# IMU.net
KiCad netlist of a schematic drawn in Altium Designer
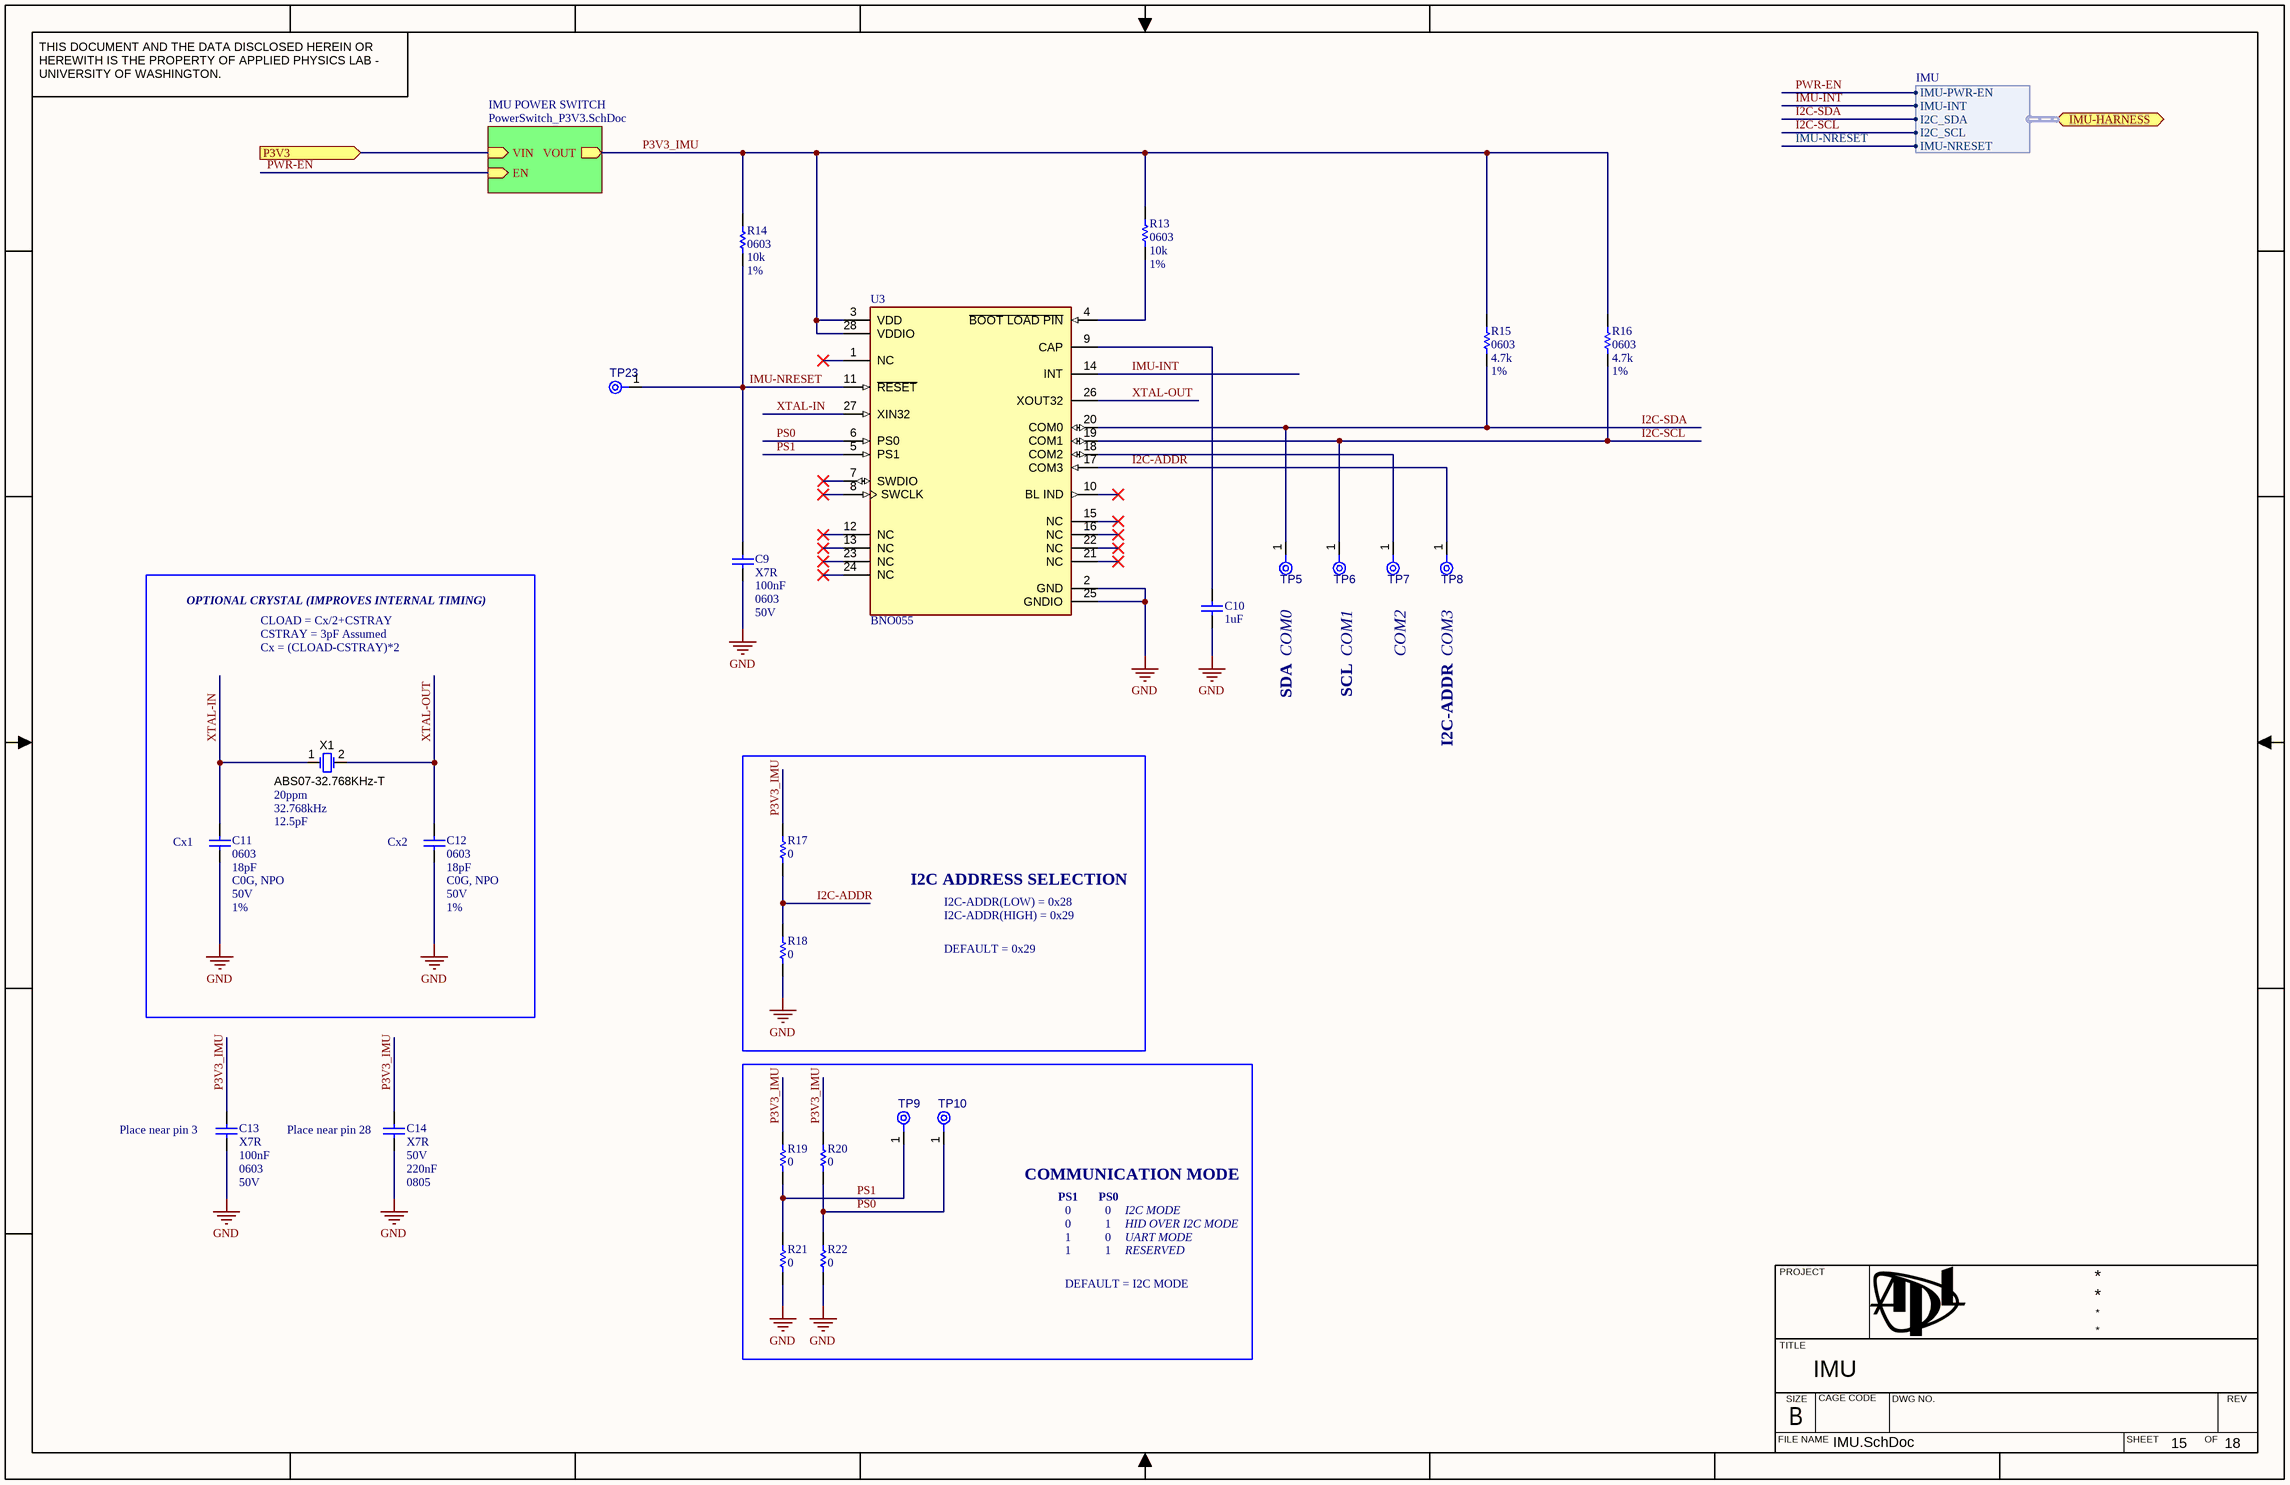
[diagram p0: IMU.SchDoc]

(export (version "E")
  (design (tool "Eeschema 10.0.6"))
  (components
    (comp (ref "C9")
      (value "100nF")
      (footprint "CAPC1608X90X40ML10T20")
      (description "Chip Capacitor, 100nF, +/- 10%, 50 V, X7R 0603 (1608 Metric)")
      (fields
        (field (name "DIELECTRIC") "X7R")
        (field (name "CASE/PACKAGE") "0603")
        (field (name "TOLERANCE") "10%")
        (field (name "VOLTAGE RATING") "50V")
        (field (name "Comment") "Capacitor 100nF +/- 10%, 50V, X7R, 0603")
      )
      (libsource (lib "Applied Physics Lab") (part "CAP-NP-2"))
    )
    (comp (ref "C10")
      (value "1uF")
      (footprint "CAPC2013X95X50ML10T25")
      (description "Chip Capacitor, 1uF, 10%, 50 V, X7R 0805 (2012 Metric)")
      (fields (field (name "TOLERANCE") "10%") (field (name "Comment") "Capacitor 1uF 10%, 50V, X7R, 0805"))
      (libsource (lib "Applied Physics Lab") (part "CAP-NP-2"))
    )
    (comp (ref "C11")
      (value "18pF")
      (footprint "CAPC1608X90X40ML10T20")
      (description "Chip Capacitor, 18pF, +/- 1%, 50 V, C0G 0603 (1608 Metric)")
      (fields
        (field (name "CASE/PACKAGE") "0603")
        (field (name "DIELECTRIC") "C0G, NPO")
        (field (name "VOLTAGE RATING") "50V")
        (field (name "TOLERANCE") "1%")
        (field (name "Comment") "Capacitor 18pF +/- 1%, 50V, C0G, 0603")
      )
      (libsource (lib "Applied Physics Lab") (part "CAP-NP-2"))
    )
    (comp (ref "C12")
      (value "18pF")
      (footprint "CAPC1608X90X40ML10T20")
      (description "Chip Capacitor, 18pF, +/- 1%, 50 V, C0G 0603 (1608 Metric)")
      (fields
        (field (name "CASE/PACKAGE") "0603")
        (field (name "DIELECTRIC") "C0G, NPO")
        (field (name "VOLTAGE RATING") "50V")
        (field (name "TOLERANCE") "1%")
        (field (name "Comment") "Capacitor 18pF +/- 1%, 50V, C0G, 0603")
      )
      (libsource (lib "Applied Physics Lab") (part "CAP-NP-2"))
    )
    (comp (ref "C13")
      (value "100nF")
      (footprint "CAPC1608X90X40ML10T20")
      (description "Chip Capacitor, 100nF, +/- 10%, 50 V, X7R 0603 (1608 Metric)")
      (fields
        (field (name "DIELECTRIC") "X7R")
        (field (name "CASE/PACKAGE") "0603")
        (field (name "TOLERANCE") "10%")
        (field (name "VOLTAGE RATING") "50V")
        (field (name "Comment") "Capacitor 100nF +/- 10%, 50V, X7R, 0603")
      )
      (libsource (lib "Applied Physics Lab") (part "CAP-NP-2"))
    )
    (comp (ref "C14")
      (value "220nF")
      (footprint "CAPC2013X95X50ML10T25")
      (description "Chip Capacitor, 220nF, 10%, 50 V, X7R 0805 (2012 Metric)")
      (fields
        (field (name "DIELECTRIC") "X7R")
        (field (name "VOLTAGE RATING") "50V")
        (field (name "CASE/PACKAGE") "0805")
        (field (name "TOLERANCE") "10%")
        (field (name "Comment") "Capacitor 220nF 10%, 50V, X7R, 0805")
      )
      (libsource (lib "Applied Physics Lab") (part "CAP-NP-2"))
    )
    (comp (ref "R13")
      (value "10k")
      (footprint "RESC1608X55X25ML10T15")
      (description "Chip Resistor, 10 KOhm, +/- 1%, 01 W, -55 to 155 degC, 0603 (1608 Metric)")
      (fields
        (field (name "CASE/PACKAGE") "0603")
        (field (name "TOLERANCE") "1%")
        (field (name "POWER") "100mW")
        (field (name "Comment") "Resistor 10k +/-1% 0603 100 mW")
      )
      (libsource (lib "Applied Physics Lab") (part "RES-2"))
    )
    (comp (ref "R14")
      (value "10k")
      (footprint "RESC1608X55X25ML10T15")
      (description "Chip Resistor, 10 KOhm, +/- 1%, 01 W, -55 to 155 degC, 0603 (1608 Metric)")
      (fields
        (field (name "CASE/PACKAGE") "0603")
        (field (name "TOLERANCE") "1%")
        (field (name "POWER") "100mW")
        (field (name "Comment") "Resistor 10k +/-1% 0603 100 mW")
      )
      (libsource (lib "Applied Physics Lab") (part "RES-2"))
    )
    (comp (ref "R15")
      (value "4.7k")
      (footprint "RESC1608X55X25ML10T15")
      (description "Chip Resistor, 4.7 KOhm, +/- 1%, 0.1 W, -55 to 155 degC, 0603 (1608 Metric)")
      (fields
        (field (name "CASE/PACKAGE") "0603")
        (field (name "TOLERANCE") "1%")
        (field (name "POWER") "100mW")
        (field (name "Comment") "Resistor 4k7 +/-1% 0603 100 mW")
      )
      (libsource (lib "Applied Physics Lab") (part "RES-2"))
    )
    (comp (ref "R16")
      (value "4.7k")
      (footprint "RESC1608X55X25ML10T15")
      (description "Chip Resistor, 4.7 KOhm, +/- 1%, 0.1 W, -55 to 155 degC, 0603 (1608 Metric)")
      (fields
        (field (name "CASE/PACKAGE") "0603")
        (field (name "TOLERANCE") "1%")
        (field (name "POWER") "100mW")
        (field (name "Comment") "Resistor 4k7 +/-1% 0603 100 mW")
      )
      (libsource (lib "Applied Physics Lab") (part "RES-2"))
    )
    (comp (ref "R17")
      (value "0")
      (footprint "RESC1608X55X25ML10T15")
      (description "Chip Resistor, 0 Ohm, 0.1 W, -55 to 155 degC, 0603 (1608 Metric)")
      (fields (field (name "TOLERANCE") "5%") (field (name "POWER") "100mW"))
      (libsource (lib "Applied Physics Lab") (part "RES-2"))
    )
    (comp (ref "R18")
      (value "0")
      (footprint "RESC1608X55X25ML10T15")
      (description "Chip Resistor, 0 Ohm, 0.1 W, -55 to 155 degC, 0603 (1608 Metric)")
      (fields (field (name "TOLERANCE") "5%") (field (name "POWER") "100mW"))
      (libsource (lib "Applied Physics Lab") (part "RES-2"))
    )
    (comp (ref "R19")
      (value "0")
      (footprint "RESC1608X55X25ML10T15")
      (description "Chip Resistor, 0 Ohm, 0.1 W, -55 to 155 degC, 0603 (1608 Metric)")
      (fields (field (name "TOLERANCE") "5%") (field (name "POWER") "100mW"))
      (libsource (lib "Applied Physics Lab") (part "RES-2"))
    )
    (comp (ref "R20")
      (value "0")
      (footprint "RESC1608X55X25ML10T15")
      (description "Chip Resistor, 0 Ohm, 0.1 W, -55 to 155 degC, 0603 (1608 Metric)")
      (fields (field (name "TOLERANCE") "5%") (field (name "POWER") "100mW"))
      (libsource (lib "Applied Physics Lab") (part "RES-2"))
    )
    (comp (ref "R21")
      (value "0")
      (footprint "RESC1608X55X25ML10T15")
      (description "Chip Resistor, 0 Ohm, 0.1 W, -55 to 155 degC, 0603 (1608 Metric)")
      (fields (field (name "TOLERANCE") "5%") (field (name "POWER") "100mW"))
      (libsource (lib "Applied Physics Lab") (part "RES-2"))
    )
    (comp (ref "R22")
      (value "0")
      (footprint "RESC1608X55X25ML10T15")
      (description "Chip Resistor, 0 Ohm, 0.1 W, -55 to 155 degC, 0603 (1608 Metric)")
      (fields (field (name "TOLERANCE") "5%") (field (name "POWER") "100mW"))
      (libsource (lib "Applied Physics Lab") (part "RES-2"))
    )
    (comp (ref "TP5")
      (value "TPAD6R-CIRCLED")
      (footprint "TP06R - Circled")
      (description "0.6mm round with a silkscreen circle.")
      (libsource (lib "Applied Physics Lab") (part "CMP-001-0001-4"))
    )
    (comp (ref "TP6")
      (value "TPAD6R-CIRCLED")
      (footprint "TP06R - Circled")
      (description "0.6mm round with a silkscreen circle.")
      (libsource (lib "Applied Physics Lab") (part "CMP-001-0001-4"))
    )
    (comp (ref "TP7")
      (value "TPAD6R-CIRCLED")
      (footprint "TP06R - Circled")
      (description "0.6mm round with a silkscreen circle.")
      (libsource (lib "Applied Physics Lab") (part "CMP-001-0001-4"))
    )
    (comp (ref "TP8")
      (value "TPAD6R-CIRCLED")
      (footprint "TP06R - Circled")
      (description "0.6mm round with a silkscreen circle.")
      (libsource (lib "Applied Physics Lab") (part "CMP-001-0001-4"))
    )
    (comp (ref "TP9")
      (value "TPAD6R-CIRCLED")
      (footprint "TP06R - Circled")
      (description "0.6mm round with a silkscreen circle.")
      (libsource (lib "Applied Physics Lab") (part "CMP-001-0001-4"))
    )
    (comp (ref "TP10")
      (value "TPAD6R-CIRCLED")
      (footprint "TP06R - Circled")
      (description "0.6mm round with a silkscreen circle.")
      (libsource (lib "Applied Physics Lab") (part "CMP-001-0001-4"))
    )
    (comp (ref "TP23")
      (value "TPAD6R-CIRCLED")
      (footprint "TP06R - Circled")
      (description "0.6mm round with a silkscreen circle.")
      (libsource (lib "Applied Physics Lab") (part "CMP-001-0001-4"))
    )
    (comp (ref "U3")
      (value "BNO055")
      (footprint "FP-BNO055-MFG")
      (description "BNO055 Series 1.7 to 3.6 V Intelligent 9-Axis Absolute Orientation Sensor-LGA-28")
      (libsource (lib "Applied Physics Lab") (part "ba837af00a0b6167256f888b31462b1"))
    )
    (comp (ref "X1")
      (value "ABS07-32.768KHz-T")
      (footprint "ABRA-ABS07-2_V")
      (fields
        (field (name "FREQUENCY TOLERANCE") "20ppm")
        (field (name "TOLERANCE") "20ppm")
        (field (name "FREQUENCY") "32.768kHz")
        (field (name "MANUFACTURER") "Abracon")
        (field (name "LOAD CAPACITANCE") "12.5pF")
      )
      (libsource (lib "Applied Physics Lab") (part "ABRA-ABS07-2"))
    )
  )
  (nets
    (net (code "2") (name "/I2C-ADDR") (class "Default")
      (node (ref "R17") (pin "1") (pinfunction "1_1") (pintype "passive"))
      (node (ref "R18") (pin "2") (pinfunction "2_2") (pintype "passive"))
      (node (ref "TP8") (pin "1") (pinfunction "TP_1") (pintype "passive"))
      (node (ref "U3") (pin "17") (pinfunction "COM3_17") (pintype "input"))
    )
    (net (code "3") (name "/I2C-SCL") (class "Default")
      (node (ref "R16") (pin "1") (pinfunction "1_1") (pintype "passive"))
      (node (ref "TP6") (pin "1") (pinfunction "TP_1") (pintype "passive"))
      (node (ref "U3") (pin "19") (pinfunction "COM1_19") (pintype "bidirectional"))
    )
    (net (code "4") (name "/I2C-SDA") (class "Default")
      (node (ref "R15") (pin "1") (pinfunction "1_1") (pintype "passive"))
      (node (ref "TP5") (pin "1") (pinfunction "TP_1") (pintype "passive"))
      (node (ref "U3") (pin "20") (pinfunction "COM0_20") (pintype "bidirectional"))
    )
    (net (code "5") (name "/IMU-INT") (class "Default")
      (node (ref "U3") (pin "14") (pinfunction "INT_14") (pintype "passive"))
    )
    (net (code "6") (name "/IMU-NRESET") (class "Default")
      (node (ref "C9") (pin "2") (pinfunction "2_2") (pintype "passive"))
      (node (ref "R14") (pin "1") (pinfunction "1_1") (pintype "passive"))
      (node (ref "TP23") (pin "1") (pinfunction "TP_1") (pintype "passive"))
      (node (ref "U3") (pin "11") (pinfunction "~{RESET}_11") (pintype "input"))
    )
    (net (code "8") (name "/P3V3_IMU") (class "Default")
      (node (ref "C13") (pin "2") (pinfunction "2_2") (pintype "passive"))
      (node (ref "C14") (pin "2") (pinfunction "2_2") (pintype "passive"))
      (node (ref "R13") (pin "2") (pinfunction "2_2") (pintype "passive"))
      (node (ref "R14") (pin "2") (pinfunction "2_2") (pintype "passive"))
      (node (ref "R15") (pin "2") (pinfunction "2_2") (pintype "passive"))
      (node (ref "R16") (pin "2") (pinfunction "2_2") (pintype "passive"))
      (node (ref "R17") (pin "2") (pinfunction "2_2") (pintype "passive"))
      (node (ref "R19") (pin "2") (pinfunction "2_2") (pintype "passive"))
      (node (ref "R20") (pin "2") (pinfunction "2_2") (pintype "passive"))
      (node (ref "U3") (pin "28") (pinfunction "VDDIO_28") (pintype "power_in"))
      (node (ref "U3") (pin "3") (pinfunction "VDD_3") (pintype "power_in"))
    )
    (net (code "9") (name "/PS0") (class "Default")
      (node (ref "R20") (pin "1") (pinfunction "1_1") (pintype "passive"))
      (node (ref "R22") (pin "2") (pinfunction "2_2") (pintype "passive"))
      (node (ref "TP10") (pin "1") (pinfunction "TP_1") (pintype "passive"))
      (node (ref "U3") (pin "6") (pinfunction "PS0_6") (pintype "input"))
    )
    (net (code "10") (name "/PS1") (class "Default")
      (node (ref "R19") (pin "1") (pinfunction "1_1") (pintype "passive"))
      (node (ref "R21") (pin "2") (pinfunction "2_2") (pintype "passive"))
      (node (ref "TP9") (pin "1") (pinfunction "TP_1") (pintype "passive"))
      (node (ref "U3") (pin "5") (pinfunction "PS1_5") (pintype "input"))
    )
    (net (code "12") (name "/XTAL-IN") (class "Default")
      (node (ref "C11") (pin "2") (pinfunction "2_2") (pintype "passive"))
      (node (ref "U3") (pin "27") (pinfunction "XIN32_27") (pintype "input"))
      (node (ref "X1") (pin "1") (pinfunction "OSC1_1") (pintype "passive"))
    )
    (net (code "13") (name "/XTAL-OUT") (class "Default")
      (node (ref "C12") (pin "2") (pinfunction "2_2") (pintype "passive"))
      (node (ref "U3") (pin "26") (pinfunction "XOUT32_26") (pintype "passive"))
      (node (ref "X1") (pin "2") (pinfunction "OSC2_2") (pintype "passive"))
    )
    (net (code "15") (name "GND") (class "Default")
      (node (ref "C10") (pin "1") (pinfunction "1_1") (pintype "passive"))
      (node (ref "C11") (pin "1") (pinfunction "1_1") (pintype "passive"))
      (node (ref "C12") (pin "1") (pinfunction "1_1") (pintype "passive"))
      (node (ref "C13") (pin "1") (pinfunction "1_1") (pintype "passive"))
      (node (ref "C14") (pin "1") (pinfunction "1_1") (pintype "passive"))
      (node (ref "C9") (pin "1") (pinfunction "1_1") (pintype "passive"))
      (node (ref "R18") (pin "1") (pinfunction "1_1") (pintype "passive"))
      (node (ref "R21") (pin "1") (pinfunction "1_1") (pintype "passive"))
      (node (ref "R22") (pin "1") (pinfunction "1_1") (pintype "passive"))
      (node (ref "U3") (pin "2") (pinfunction "GND_2") (pintype "power_in"))
      (node (ref "U3") (pin "25") (pinfunction "GNDIO_25") (pintype "power_in"))
    )
    (net (code "16") (name "Net-(TP7-TP)") (class "Default")
      (node (ref "TP7") (pin "1") (pinfunction "TP_1") (pintype "passive"))
      (node (ref "U3") (pin "18") (pinfunction "COM2_18") (pintype "bidirectional"))
    )
    (net (code "17") (name "Net-(U3-CAP)") (class "Default")
      (node (ref "C10") (pin "2") (pinfunction "2_2") (pintype "passive"))
      (node (ref "U3") (pin "9") (pinfunction "CAP_9") (pintype "passive"))
    )
    (net (code "18") (name "Net-(U3-~{BOOT_LOAD_PIN})") (class "Default")
      (node (ref "R13") (pin "1") (pinfunction "1_1") (pintype "passive"))
      (node (ref "U3") (pin "4") (pinfunction "~{BOOT_LOAD_PIN}_4") (pintype "input"))
    )
    (net (code "19") (name "unconnected-(U3-BL_IND-Pad10)") (class "Default")
      (node (ref "U3") (pin "10") (pinfunction "BL_IND_10") (pintype "output+no_connect"))
    )
    (net (code "20") (name "unconnected-(U3-NC-Pad1)") (class "Default")
      (node (ref "U3") (pin "1") (pinfunction "NC_1") (pintype "passive+no_connect"))
    )
    (net (code "21") (name "unconnected-(U3-NC-Pad12)") (class "Default")
      (node (ref "U3") (pin "12") (pinfunction "NC_12") (pintype "passive+no_connect"))
    )
    (net (code "22") (name "unconnected-(U3-NC-Pad13)") (class "Default")
      (node (ref "U3") (pin "13") (pinfunction "NC_13") (pintype "passive+no_connect"))
    )
    (net (code "23") (name "unconnected-(U3-NC-Pad15)") (class "Default")
      (node (ref "U3") (pin "15") (pinfunction "NC_15") (pintype "passive+no_connect"))
    )
    (net (code "24") (name "unconnected-(U3-NC-Pad16)") (class "Default")
      (node (ref "U3") (pin "16") (pinfunction "NC_16") (pintype "passive+no_connect"))
    )
    (net (code "25") (name "unconnected-(U3-NC-Pad21)") (class "Default")
      (node (ref "U3") (pin "21") (pinfunction "NC_21") (pintype "passive+no_connect"))
    )
    (net (code "26") (name "unconnected-(U3-NC-Pad22)") (class "Default")
      (node (ref "U3") (pin "22") (pinfunction "NC_22") (pintype "passive+no_connect"))
    )
    (net (code "27") (name "unconnected-(U3-NC-Pad23)") (class "Default")
      (node (ref "U3") (pin "23") (pinfunction "NC_23") (pintype "passive+no_connect"))
    )
    (net (code "28") (name "unconnected-(U3-NC-Pad24)") (class "Default")
      (node (ref "U3") (pin "24") (pinfunction "NC_24") (pintype "passive+no_connect"))
    )
    (net (code "29") (name "unconnected-(U3-SWCLK-Pad8)") (class "Default")
      (node (ref "U3") (pin "8") (pinfunction "SWCLK_8") (pintype "input+no_connect"))
    )
    (net (code "30") (name "unconnected-(U3-SWDIO-Pad7)") (class "Default")
      (node (ref "U3") (pin "7") (pinfunction "SWDIO_7") (pintype "bidirectional+no_connect"))
    )
  )
)
